# CPU_LPC1776_1.net
KiCad netlist of a schematic drawn in Altium Designer
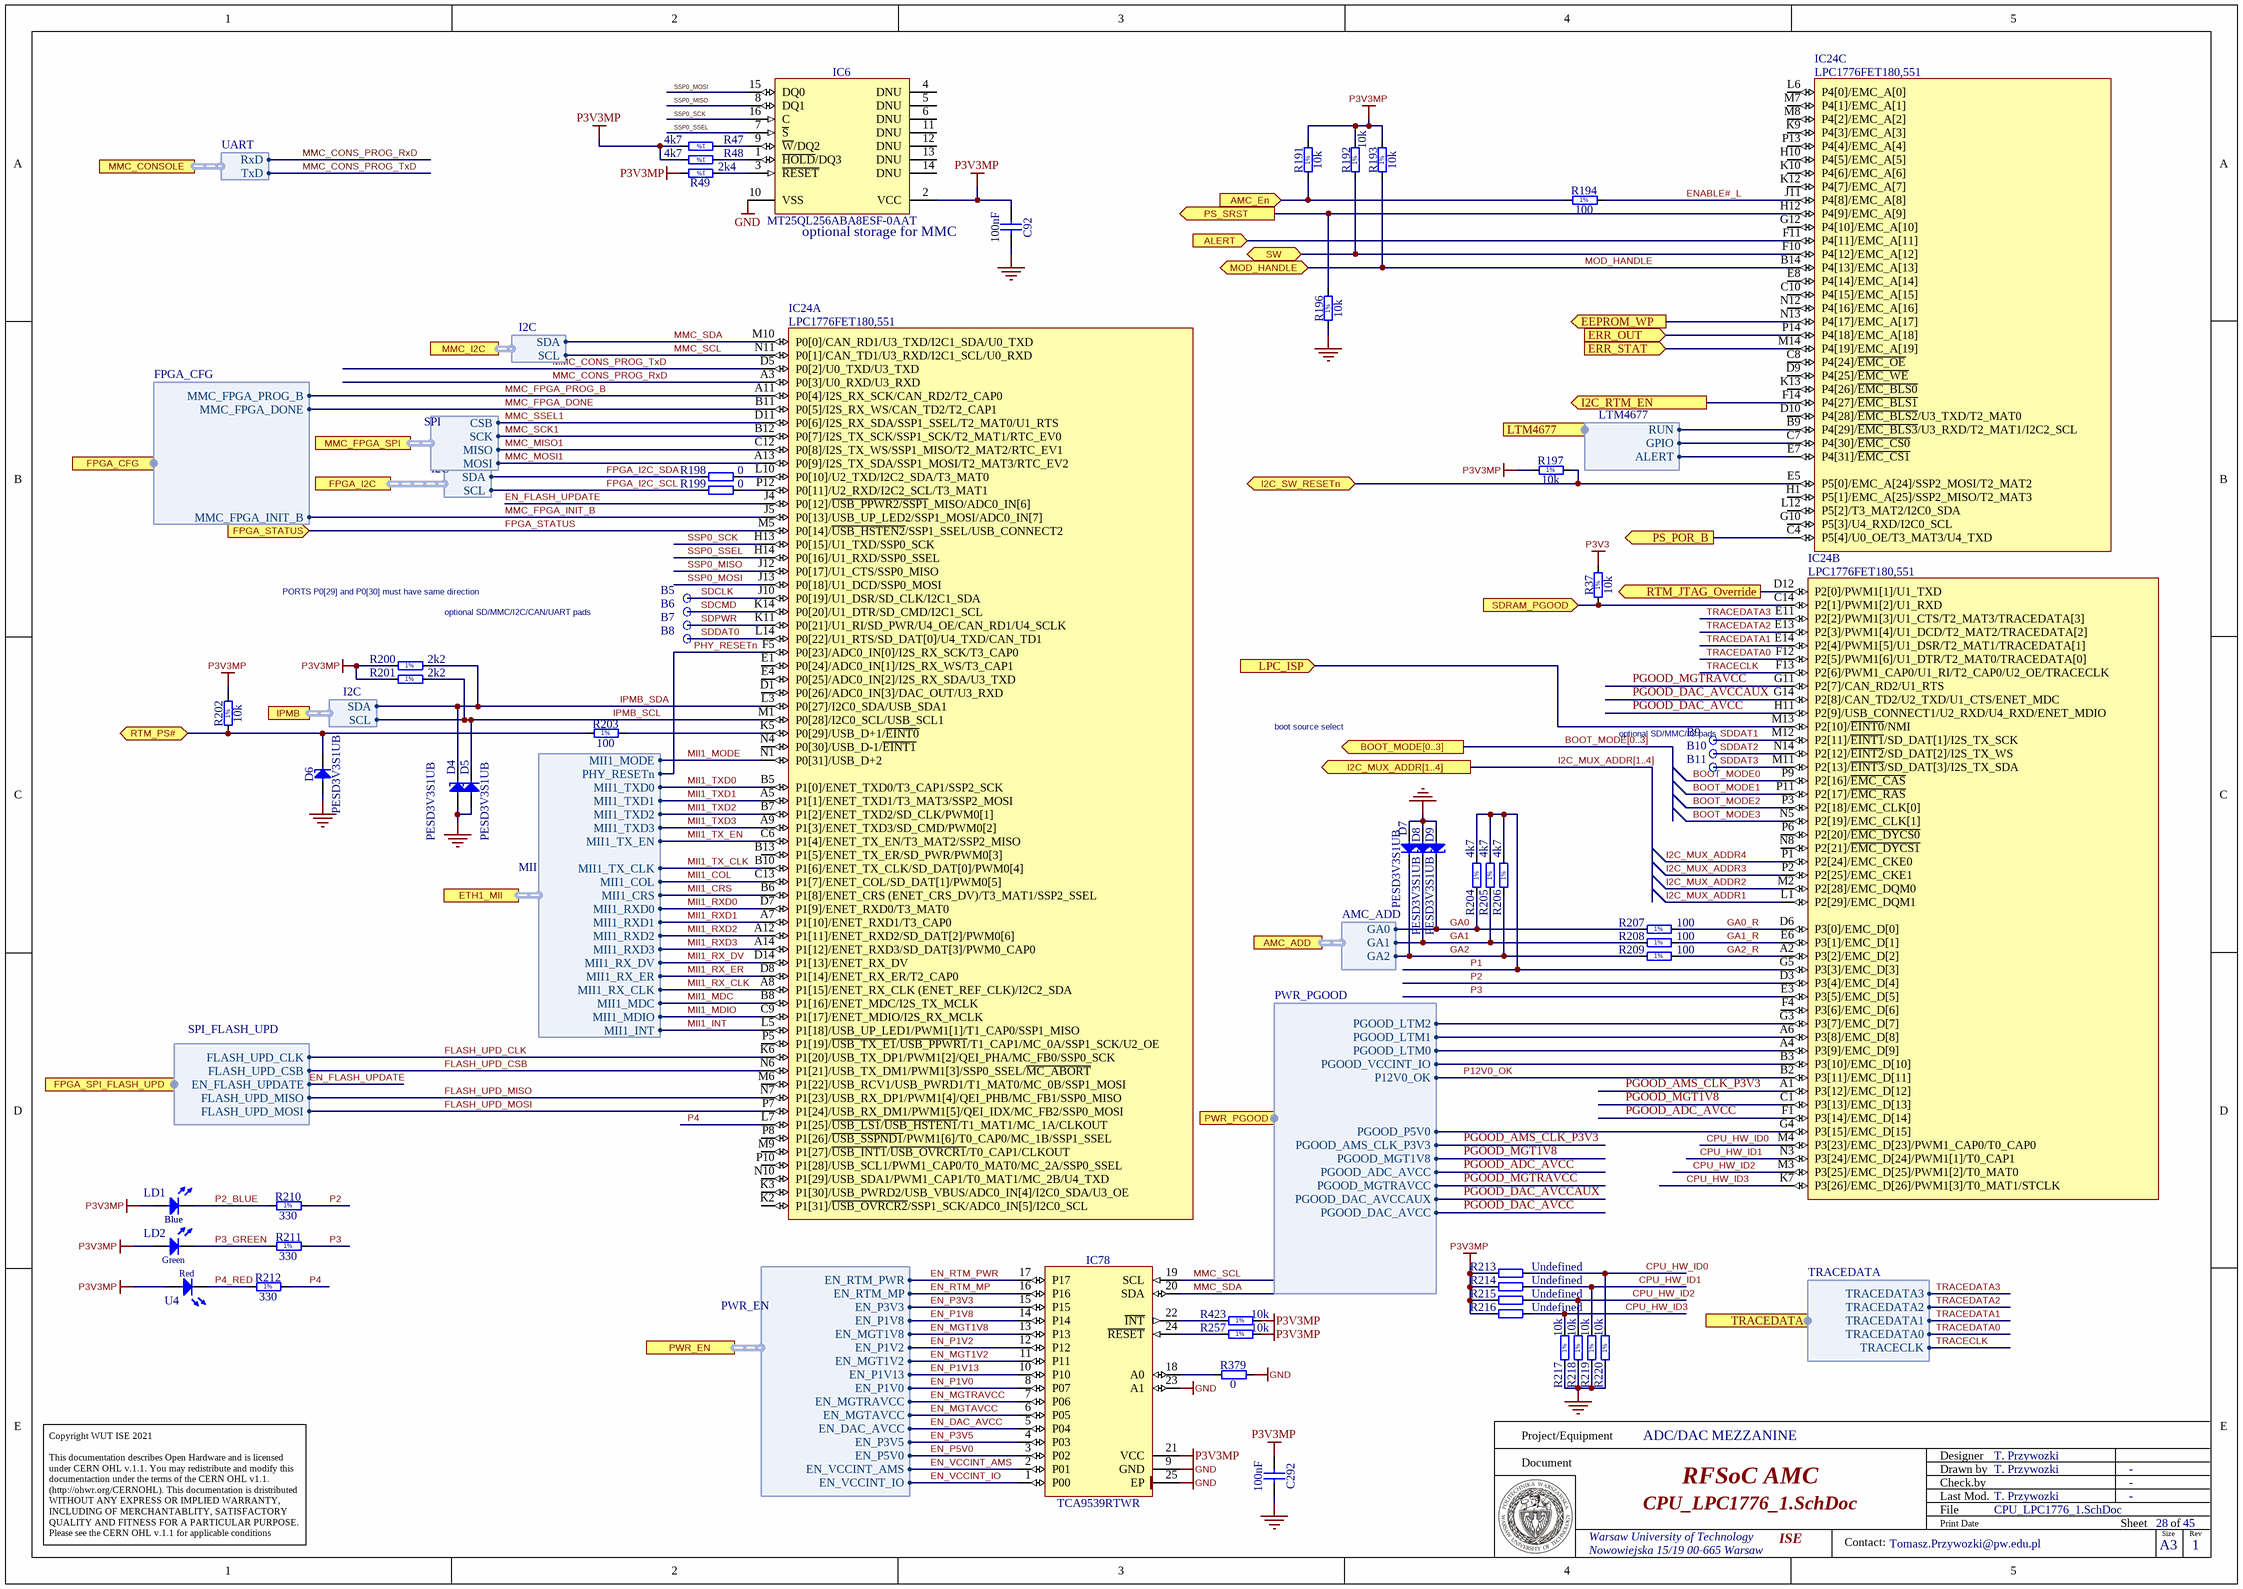
[diagram p0: CPU_LPC1776_1.SchDoc]

(export (version "E")
  (design (tool "Eeschema 10.0.6"))
  (components
    (comp (ref "B5")
      (value "SMD_PAD_D1MM")
      (footprint "C100")
      (libsource (lib "altium-import") (part "root_0__*"))
    )
    (comp (ref "B6")
      (value "SMD_PAD_D1MM")
      (footprint "C100")
      (libsource (lib "altium-import") (part "root_0__*"))
    )
    (comp (ref "B7")
      (value "SMD_PAD_D1MM")
      (footprint "C100")
      (libsource (lib "altium-import") (part "root_0__*"))
    )
    (comp (ref "B8")
      (value "SMD_PAD_D1MM")
      (footprint "C100")
      (libsource (lib "altium-import") (part "root_0__*"))
    )
    (comp (ref "B9")
      (value "SMD_PAD_D1MM")
      (footprint "C100")
      (libsource (lib "altium-import") (part "root_0__*"))
    )
    (comp (ref "B10")
      (value "SMD_PAD_D1MM")
      (footprint "C100")
      (libsource (lib "altium-import") (part "root_0__*"))
    )
    (comp (ref "B11")
      (value "SMD_PAD_D1MM")
      (footprint "C100")
      (libsource (lib "altium-import") (part "root_0__*"))
    )
    (comp (ref "C92")
      (value "100nF")
      (footprint "CAPC0603X33N")
      (description "Non-polarised capacitor")
      (fields
        (field (name "MANUFACTURER PART NUMBER") "CC0201_100NF_6.3V_10%_X5R")
        (field (name "MANUFACTURER") "GENERIC")
        (field (name "AUTHOR") "CERN DEM JLC")
      )
      (libsource (lib "Capacitors") (part "Capacitor - non polarized"))
    )
    (comp (ref "C292")
      (value "100nF")
      (footprint "CAPC0603X33N")
      (description "Non-polarised capacitor")
      (fields
        (field (name "MANUFACTURER PART NUMBER") "CC0201_100NF_6.3V_10%_X5R")
        (field (name "MANUFACTURER") "GENERIC")
        (field (name "AUTHOR") "CERN DEM JLC")
      )
      (libsource (lib "Capacitors") (part "Capacitor - non polarized"))
    )
    (comp (ref "D4")
      (value "PESD3V3S1UB")
      (footprint "SODFL1608X65N")
      (description "ESD protection diode")
      (fields
        (field (name "MANUFACTURER") "NXP SEMICONDUCTORS")
        (field (name "VOLTAGE") "3V3")
        (field (name "AUTHOR") "CERN DEM JLC")
      )
      (libsource (lib "ICs And Semiconductors") (part "Diode ESD"))
    )
    (comp (ref "D5")
      (value "PESD3V3S1UB")
      (footprint "SODFL1608X65N")
      (description "ESD protection diode")
      (fields
        (field (name "MANUFACTURER") "NXP SEMICONDUCTORS")
        (field (name "VOLTAGE") "3V3")
        (field (name "AUTHOR") "CERN DEM JLC")
      )
      (libsource (lib "ICs And Semiconductors") (part "Diode ESD"))
    )
    (comp (ref "D6")
      (value "PESD3V3S1UB")
      (footprint "SODFL1608X65N")
      (description "ESD protection diode")
      (fields
        (field (name "MANUFACTURER") "NXP SEMICONDUCTORS")
        (field (name "VOLTAGE") "3V3")
        (field (name "AUTHOR") "CERN DEM JLC")
      )
      (libsource (lib "ICs And Semiconductors") (part "Diode ESD"))
    )
    (comp (ref "D7")
      (value "PESD3V3S1UB")
      (footprint "SODFL1608X65N")
      (description "ESD protection diode")
      (fields
        (field (name "MANUFACTURER") "NXP SEMICONDUCTORS")
        (field (name "VOLTAGE") "3V3")
        (field (name "AUTHOR") "CERN DEM JLC")
      )
      (libsource (lib "ICs And Semiconductors") (part "Diode ESD"))
    )
    (comp (ref "D8")
      (value "PESD3V3S1UB")
      (footprint "SODFL1608X65N")
      (description "ESD protection diode")
      (fields
        (field (name "MANUFACTURER") "NXP SEMICONDUCTORS")
        (field (name "VOLTAGE") "3V3")
        (field (name "AUTHOR") "CERN DEM JLC")
      )
      (libsource (lib "ICs And Semiconductors") (part "Diode ESD"))
    )
    (comp (ref "D9")
      (value "PESD3V3S1UB")
      (footprint "SODFL1608X65N")
      (description "ESD protection diode")
      (fields
        (field (name "MANUFACTURER") "NXP SEMICONDUCTORS")
        (field (name "VOLTAGE") "3V3")
        (field (name "AUTHOR") "CERN DEM JLC")
      )
      (libsource (lib "ICs And Semiconductors") (part "Diode ESD"))
    )
    (comp (ref "IC6")
      (value "MT25QL256ABA8ESF-0AAT")
      (footprint "SOIC127P1030X265-16N")
      (description "256Mbit (32MB), 2.7V-3.6V, Multiple I/O Serial NOR Flash Memory,with Reset# & Hold#")
      (fields (field (name "MANUFACTURER") "MICRON TECHNOLOGY") (field (name "AUTHOR") "CERN DEM JLC"))
      (libsource (lib "ICs And Semiconductors") (part "MT25QL256ABA8ESF"))
    )
    (comp (ref "IC24")
      (value "LPC1776FET180,551")
      (footprint "BGA180C80P14X14_1200X1200X120")
      (fields (field (name "MANUFACTURER") "NXP SEMICONDUCTORS") (field (name "AUTHOR") "CERN DEM JMW"))
      (libsource (lib "ICs And Semiconductors") (part "LPC1776FET180,551"))
    )
    (comp (ref "IC78")
      (value "TCA9539RTWR")
      (footprint "QFN50P400X400X80-25N-S255")
      (description "Low-Voltage 16-Bit I2C and SMBus I/O Expander")
      (fields (field (name "MANUFACTURER") "TEXAS INSTRUMENTS") (field (name "AUTHOR") "CERN DEM MR"))
      (libsource (lib "ICs And Semiconductors") (part "TCA9539RTWR"))
    )
    (comp (ref "LD1")
      (value "Blue")
      (footprint "LED_AVAGO_HSMR-C120")
      (description "LED Blue 1C 2A")
      (fields
        (field (name "MANUFACTURER PART NUMBER") "HSMR-C120")
        (field (name "MANUFACTURER") "AVAGO TECHNOLOGIES")
        (field (name "AUTHOR") "CERN DEM JLC")
      )
      (libsource (lib "ICs And Semiconductors") (part "LED Blue 1C 2A"))
    )
    (comp (ref "LD2")
      (value "Green")
      (footprint "LED_AVAGO_HSME-C120")
      (description "LED Green 1C 2A")
      (fields
        (field (name "MANUFACTURER PART NUMBER") "HSME-C120")
        (field (name "MANUFACTURER") "AVAGO TECHNOLOGIES")
        (field (name "AUTHOR") "CERN DEM JMW")
      )
      (libsource (lib "ICs And Semiconductors") (part "LED Green 1C 2A"))
    )
    (comp (ref "R37")
      (value "10k")
      (footprint "RESC1005X40N")
      (description "Resistor - 1%")
      (fields
        (field (name "MANUFACTURER PART NUMBER") "R0402_10K_1%_0.0625W_100PPM")
        (field (name "MANUFACTURER") "GENERIC")
        (field (name "AUTHOR") "CERN DEM JLC")
      )
      (libsource (lib "Resistors") (part "Resistor - 1%"))
    )
    (comp (ref "R47")
      (value "4k7")
      (footprint "RESC1005X40N")
      (description "Resistor - 1%")
      (fields
        (field (name "MANUFACTURER PART NUMBER") "R0402_4K7_1%_0.0625W_100PPM")
        (field (name "MANUFACTURER") "GENERIC")
        (field (name "AUTHOR") "CERN DEM JLC")
      )
      (libsource (lib "Resistors") (part "Resistor - 1%"))
    )
    (comp (ref "R48")
      (value "4k7")
      (footprint "RESC1005X40N")
      (description "Resistor - 1%")
      (fields
        (field (name "MANUFACTURER PART NUMBER") "R0402_4K7_1%_0.0625W_100PPM")
        (field (name "MANUFACTURER") "GENERIC")
        (field (name "AUTHOR") "CERN DEM JLC")
      )
      (libsource (lib "Resistors") (part "Resistor - 1%"))
    )
    (comp (ref "R49")
      (value "2k4")
      (footprint "RESC1005X40N")
      (description "Resistor - 1%")
      (fields
        (field (name "MANUFACTURER PART NUMBER") "R0402_2K4_1%_0.0625W_100PPM")
        (field (name "MANUFACTURER") "GENERIC")
        (field (name "AUTHOR") "CERN DEM JLC")
      )
      (libsource (lib "Resistors") (part "Resistor - 1%"))
    )
    (comp (ref "R191")
      (value "10k")
      (footprint "RESC1005X40N")
      (description "Resistor - 1%")
      (fields
        (field (name "MANUFACTURER PART NUMBER") "R0402_10K_1%_0.0625W_100PPM")
        (field (name "MANUFACTURER") "GENERIC")
        (field (name "AUTHOR") "CERN DEM JLC")
      )
      (libsource (lib "Resistors") (part "Resistor - 1%"))
    )
    (comp (ref "R192")
      (value "10k")
      (footprint "RESC1005X40N")
      (description "Resistor - 1%")
      (fields
        (field (name "MANUFACTURER PART NUMBER") "R0402_10K_1%_0.0625W_100PPM")
        (field (name "MANUFACTURER") "GENERIC")
        (field (name "AUTHOR") "CERN DEM JLC")
      )
      (libsource (lib "Resistors") (part "Resistor - 1%"))
    )
    (comp (ref "R193")
      (value "10k")
      (footprint "RESC1005X40N")
      (description "Resistor - 1%")
      (fields
        (field (name "MANUFACTURER PART NUMBER") "R0402_10K_1%_0.0625W_100PPM")
        (field (name "MANUFACTURER") "GENERIC")
        (field (name "AUTHOR") "CERN DEM JLC")
      )
      (libsource (lib "Resistors") (part "Resistor - 1%"))
    )
    (comp (ref "R194")
      (value "100")
      (footprint "RESC1005X40N")
      (description "Resistor - 1%")
      (fields
        (field (name "MANUFACTURER PART NUMBER") "R0402_100R_1%_0.1W_100PPM_50V")
        (field (name "MANUFACTURER") "GENERIC")
        (field (name "AUTHOR") "CERN DEM JLC")
      )
      (libsource (lib "Resistors") (part "Resistor - 1%"))
    )
    (comp (ref "R196")
      (value "10k")
      (footprint "RESC1005X40N")
      (description "Resistor - 1%")
      (fields
        (field (name "MANUFACTURER PART NUMBER") "R0402_10K_1%_0.0625W_100PPM")
        (field (name "MANUFACTURER") "GENERIC")
        (field (name "AUTHOR") "CERN DEM JLC")
      )
      (libsource (lib "Resistors") (part "Resistor - 1%"))
    )
    (comp (ref "R197")
      (value "10k")
      (footprint "RESC1005X40N")
      (description "Resistor - 1%")
      (fields
        (field (name "MANUFACTURER PART NUMBER") "R0402_10K_1%_0.0625W_100PPM")
        (field (name "MANUFACTURER") "GENERIC")
        (field (name "AUTHOR") "CERN DEM JLC")
      )
      (libsource (lib "Resistors") (part "Resistor - 1%"))
    )
    (comp (ref "R198")
      (value "0")
      (footprint "RESC1005X40N")
      (description "Resistor")
      (fields
        (field (name "MANUFACTURER PART NUMBER") "R0402_0R_JUMPER")
        (field (name "MANUFACTURER") "GENERIC")
        (field (name "AUTHOR") "CERN DEM JLC")
      )
      (libsource (lib "Resistors") (part "Resistor"))
    )
    (comp (ref "R199")
      (value "0")
      (footprint "RESC1005X40N")
      (description "Resistor")
      (fields
        (field (name "MANUFACTURER PART NUMBER") "R0402_0R_JUMPER")
        (field (name "MANUFACTURER") "GENERIC")
        (field (name "AUTHOR") "CERN DEM JLC")
      )
      (libsource (lib "Resistors") (part "Resistor"))
    )
    (comp (ref "R200")
      (value "2k2")
      (footprint "RESC1005X40N")
      (description "Resistor - 1%")
      (fields
        (field (name "MANUFACTURER PART NUMBER") "R0402_2K2_1%_0.0625W_100PPM")
        (field (name "MANUFACTURER") "GENERIC")
        (field (name "AUTHOR") "CERN DEM JLC")
      )
      (libsource (lib "Resistors") (part "Resistor - 1%"))
    )
    (comp (ref "R201")
      (value "2k2")
      (footprint "RESC1005X40N")
      (description "Resistor - 1%")
      (fields
        (field (name "MANUFACTURER PART NUMBER") "R0402_2K2_1%_0.0625W_100PPM")
        (field (name "MANUFACTURER") "GENERIC")
        (field (name "AUTHOR") "CERN DEM JLC")
      )
      (libsource (lib "Resistors") (part "Resistor - 1%"))
    )
    (comp (ref "R202")
      (value "10k")
      (footprint "RESC1005X40N")
      (description "Resistor - 1%")
      (fields
        (field (name "MANUFACTURER PART NUMBER") "R0402_10K_1%_0.0625W_100PPM")
        (field (name "MANUFACTURER") "GENERIC")
        (field (name "AUTHOR") "CERN DEM JLC")
      )
      (libsource (lib "Resistors") (part "Resistor - 1%"))
    )
    (comp (ref "R203")
      (value "100")
      (footprint "RESC1005X40N")
      (description "Resistor - 1%")
      (fields
        (field (name "MANUFACTURER PART NUMBER") "R0402_100R_1%_0.1W_100PPM_50V")
        (field (name "MANUFACTURER") "GENERIC")
        (field (name "AUTHOR") "CERN DEM JLC")
      )
      (libsource (lib "Resistors") (part "Resistor - 1%"))
    )
    (comp (ref "R204")
      (value "4k7")
      (footprint "RESC1005X40N")
      (description "Resistor - 1%")
      (fields
        (field (name "MANUFACTURER PART NUMBER") "R0402_4K7_1%_0.0625W_100PPM")
        (field (name "MANUFACTURER") "GENERIC")
        (field (name "AUTHOR") "CERN DEM JLC")
      )
      (libsource (lib "Resistors") (part "Resistor - 1%"))
    )
    (comp (ref "R205")
      (value "4k7")
      (footprint "RESC1005X40N")
      (description "Resistor - 1%")
      (fields
        (field (name "MANUFACTURER PART NUMBER") "R0402_4K7_1%_0.0625W_100PPM")
        (field (name "MANUFACTURER") "GENERIC")
        (field (name "AUTHOR") "CERN DEM JLC")
      )
      (libsource (lib "Resistors") (part "Resistor - 1%"))
    )
    (comp (ref "R206")
      (value "4k7")
      (footprint "RESC1005X40N")
      (description "Resistor - 1%")
      (fields
        (field (name "MANUFACTURER PART NUMBER") "R0402_4K7_1%_0.0625W_100PPM")
        (field (name "MANUFACTURER") "GENERIC")
        (field (name "AUTHOR") "CERN DEM JLC")
      )
      (libsource (lib "Resistors") (part "Resistor - 1%"))
    )
    (comp (ref "R207")
      (value "100")
      (footprint "RESC1005X40N")
      (description "Resistor - 1%")
      (fields
        (field (name "MANUFACTURER PART NUMBER") "R0402_100R_1%_0.1W_100PPM_50V")
        (field (name "MANUFACTURER") "GENERIC")
        (field (name "AUTHOR") "CERN DEM JLC")
      )
      (libsource (lib "Resistors") (part "Resistor - 1%"))
    )
    (comp (ref "R208")
      (value "100")
      (footprint "RESC1005X40N")
      (description "Resistor - 1%")
      (fields
        (field (name "MANUFACTURER PART NUMBER") "R0402_100R_1%_0.1W_100PPM_50V")
        (field (name "MANUFACTURER") "GENERIC")
        (field (name "AUTHOR") "CERN DEM JLC")
      )
      (libsource (lib "Resistors") (part "Resistor - 1%"))
    )
    (comp (ref "R209")
      (value "100")
      (footprint "RESC1005X40N")
      (description "Resistor - 1%")
      (fields
        (field (name "MANUFACTURER PART NUMBER") "R0402_100R_1%_0.1W_100PPM_50V")
        (field (name "MANUFACTURER") "GENERIC")
        (field (name "AUTHOR") "CERN DEM JLC")
      )
      (libsource (lib "Resistors") (part "Resistor - 1%"))
    )
    (comp (ref "R210")
      (value "330")
      (footprint "RESC1005X40N")
      (description "Resistor - 1%")
      (fields
        (field (name "MANUFACTURER PART NUMBER") "R0402_330R_1%_0.0625W_100PPM")
        (field (name "MANUFACTURER") "GENERIC")
        (field (name "AUTHOR") "CERN DEM JLC")
      )
      (libsource (lib "Resistors") (part "Resistor - 1%"))
    )
    (comp (ref "R211")
      (value "330")
      (footprint "RESC1005X40N")
      (description "Resistor - 1%")
      (fields
        (field (name "MANUFACTURER PART NUMBER") "R0402_330R_1%_0.0625W_100PPM")
        (field (name "MANUFACTURER") "GENERIC")
        (field (name "AUTHOR") "CERN DEM JLC")
      )
      (libsource (lib "Resistors") (part "Resistor - 1%"))
    )
    (comp (ref "R212")
      (value "330")
      (footprint "RESC1005X40N")
      (description "Resistor - 1%")
      (fields
        (field (name "MANUFACTURER PART NUMBER") "R0402_330R_1%_0.0625W_100PPM")
        (field (name "MANUFACTURER") "GENERIC")
        (field (name "AUTHOR") "CERN DEM JLC")
      )
      (libsource (lib "Resistors") (part "Resistor - 1%"))
    )
    (comp (ref "R213")
      (value "Undefined")
      (footprint "RESC1005X40N")
      (description "Resistor")
      (fields (field (name "PART NUMBER") "R0402_NO-VALUE") (field (name "AUTHOR") "CERN DEM JLC"))
      (libsource (lib "Resistors") (part "Resistor"))
    )
    (comp (ref "R214")
      (value "Undefined")
      (footprint "RESC1005X40N")
      (description "Resistor")
      (fields (field (name "PART NUMBER") "R0402_NO-VALUE") (field (name "AUTHOR") "CERN DEM JLC"))
      (libsource (lib "Resistors") (part "Resistor"))
    )
    (comp (ref "R215")
      (value "Undefined")
      (footprint "RESC1005X40N")
      (description "Resistor")
      (fields (field (name "PART NUMBER") "R0402_NO-VALUE") (field (name "AUTHOR") "CERN DEM JLC"))
      (libsource (lib "Resistors") (part "Resistor"))
    )
    (comp (ref "R216")
      (value "Undefined")
      (footprint "RESC1005X40N")
      (description "Resistor")
      (fields (field (name "PART NUMBER") "R0402_NO-VALUE") (field (name "AUTHOR") "CERN DEM JLC"))
      (libsource (lib "Resistors") (part "Resistor"))
    )
    (comp (ref "R217")
      (value "10k")
      (footprint "RESC1005X40N")
      (description "Resistor - 1%")
      (fields
        (field (name "MANUFACTURER PART NUMBER") "R0402_10K_1%_0.0625W_100PPM")
        (field (name "MANUFACTURER") "GENERIC")
        (field (name "AUTHOR") "CERN DEM JLC")
      )
      (libsource (lib "Resistors") (part "Resistor - 1%"))
    )
    (comp (ref "R218")
      (value "10k")
      (footprint "RESC1005X40N")
      (description "Resistor - 1%")
      (fields
        (field (name "MANUFACTURER PART NUMBER") "R0402_10K_1%_0.0625W_100PPM")
        (field (name "MANUFACTURER") "GENERIC")
        (field (name "AUTHOR") "CERN DEM JLC")
      )
      (libsource (lib "Resistors") (part "Resistor - 1%"))
    )
    (comp (ref "R219")
      (value "10k")
      (footprint "RESC1005X40N")
      (description "Resistor - 1%")
      (fields
        (field (name "MANUFACTURER PART NUMBER") "R0402_10K_1%_0.0625W_100PPM")
        (field (name "MANUFACTURER") "GENERIC")
        (field (name "AUTHOR") "CERN DEM JLC")
      )
      (libsource (lib "Resistors") (part "Resistor - 1%"))
    )
    (comp (ref "R220")
      (value "10k")
      (footprint "RESC1005X40N")
      (description "Resistor - 1%")
      (fields
        (field (name "MANUFACTURER PART NUMBER") "R0402_10K_1%_0.0625W_100PPM")
        (field (name "MANUFACTURER") "GENERIC")
        (field (name "AUTHOR") "CERN DEM JLC")
      )
      (libsource (lib "Resistors") (part "Resistor - 1%"))
    )
    (comp (ref "R257")
      (value "10k")
      (footprint "RESC1005X40N")
      (description "Resistor - 1%")
      (fields
        (field (name "MANUFACTURER PART NUMBER") "R0402_10K_1%_0.0625W_100PPM")
        (field (name "MANUFACTURER") "GENERIC")
        (field (name "AUTHOR") "CERN DEM JLC")
      )
      (libsource (lib "Resistors") (part "Resistor - 1%"))
    )
    (comp (ref "R379")
      (value "0")
      (footprint "RESC1005X40N")
      (description "Resistor")
      (fields
        (field (name "PART NUMBER") "R0402_0R_JUMPER")
        (field (name "MANUFACTURER") "GENERIC")
        (field (name "AUTHOR") "CERN DEM JLC")
      )
      (libsource (lib "Resistors") (part "Resistor"))
    )
    (comp (ref "R423")
      (value "10k")
      (footprint "RESC1005X40N")
      (description "Resistor - 1%")
      (fields
        (field (name "MANUFACTURER PART NUMBER") "R0402_10K_1%_0.0625W_100PPM")
        (field (name "MANUFACTURER") "GENERIC")
        (field (name "AUTHOR") "CERN DEM JLC")
      )
      (libsource (lib "Resistors") (part "Resistor - 1%"))
    )
    (comp (ref "U4")
      (value "Red")
      (footprint "LED_OSRAM_LS Q976")
      (description "LED Red 1C 2A")
      (fields
        (field (name "MANUFACTURER PART NUMBER") "LS Q976-NR-1")
        (field (name "MANUFACTURER") "OSRAM")
        (field (name "AUTHOR") "CERN DEM JLC")
      )
      (libsource (lib "ICs And Semiconductors") (part "LED Red 1C 2A"))
    )
  )
  (nets
    (net (code "12") (name "/ALERT") (class "Default")
      (node (ref "IC24") (pin "F11") (pinfunction "P4[11]/EMC_A[11]_F11") (pintype "bidirectional"))
    )
    (net (code "13") (name "/AMC_En") (class "Default")
      (node (ref "R191") (pin "1") (pinfunction "1_1") (pintype "passive"))
      (node (ref "R194") (pin "1") (pinfunction "1_1") (pintype "passive"))
    )
    (net (code "14") (name "/BOOT_MODE0") (class "Default")
      (node (ref "IC24") (pin "P9") (pinfunction "P2[16]/~{EMC_CAS}_P9") (pintype "bidirectional"))
    )
    (net (code "15") (name "/BOOT_MODE1") (class "Default")
      (node (ref "IC24") (pin "P11") (pinfunction "P2[17]/~{EMC_RAS}_P11") (pintype "bidirectional"))
    )
    (net (code "16") (name "/BOOT_MODE2") (class "Default")
      (node (ref "IC24") (pin "P3") (pinfunction "P2[18]/EMC_CLK[0]_P3") (pintype "bidirectional"))
    )
    (net (code "17") (name "/BOOT_MODE3") (class "Default")
      (node (ref "IC24") (pin "N5") (pinfunction "P2[19]/EMC_CLK[1]_N5") (pintype "bidirectional"))
    )
    (net (code "19") (name "/CPU_HW_ID0") (class "Default")
      (node (ref "IC24") (pin "M4") (pinfunction "P3[23]/EMC_D[23]/PWM1_CAP0/T0_CAP0_M4") (pintype "bidirectional"))
      (node (ref "R213") (pin "2") (pinfunction "2_2") (pintype "passive"))
      (node (ref "R220") (pin "2") (pinfunction "2_2") (pintype "passive"))
    )
    (net (code "20") (name "/CPU_HW_ID1") (class "Default")
      (node (ref "IC24") (pin "N3") (pinfunction "P3[24]/EMC_D[24]/PWM1[1]/T0_CAP1_N3") (pintype "bidirectional"))
      (node (ref "R214") (pin "2") (pinfunction "2_2") (pintype "passive"))
      (node (ref "R219") (pin "2") (pinfunction "2_2") (pintype "passive"))
    )
    (net (code "21") (name "/CPU_HW_ID2") (class "Default")
      (node (ref "IC24") (pin "M3") (pinfunction "P3[25]/EMC_D[25]/PWM1[2]/T0_MAT0_M3") (pintype "bidirectional"))
      (node (ref "R215") (pin "2") (pinfunction "2_2") (pintype "passive"))
      (node (ref "R218") (pin "2") (pinfunction "2_2") (pintype "passive"))
    )
    (net (code "22") (name "/CPU_HW_ID3") (class "Default")
      (node (ref "IC24") (pin "K7") (pinfunction "P3[26]/EMC_D[26]/PWM1[3]/T0_MAT1/STCLK_K7") (pintype "bidirectional"))
      (node (ref "R216") (pin "2") (pinfunction "2_2") (pintype "passive"))
      (node (ref "R217") (pin "2") (pinfunction "2_2") (pintype "passive"))
    )
    (net (code "23") (name "/EEPROM_WP") (class "Default")
      (node (ref "IC24") (pin "N13") (pinfunction "P4[17]/EMC_A[17]_N13") (pintype "bidirectional"))
    )
    (net (code "24") (name "/ENABLE#_L") (class "Default")
      (node (ref "IC24") (pin "J11") (pinfunction "P4[8]/EMC_A[8]_J11") (pintype "bidirectional"))
      (node (ref "R194") (pin "2") (pinfunction "2_2") (pintype "passive"))
    )
    (net (code "25") (name "/EN_DAC_AVCC") (class "Default")
      (node (ref "IC78") (pin "5") (pinfunction "P04_5") (pintype "bidirectional"))
    )
    (net (code "26") (name "/EN_FLASH_UPDATE") (class "Default")
      (node (ref "IC24") (pin "J4") (pinfunction "P0[12]/~{USB_PPWR2/SSP1}_MISO/ADC0_IN[6]_J4") (pintype "bidirectional"))
    )
    (net (code "27") (name "/EN_MGT1V2") (class "Default")
      (node (ref "IC78") (pin "11") (pinfunction "P11_11") (pintype "bidirectional"))
    )
    (net (code "28") (name "/EN_MGT1V8") (class "Default")
      (node (ref "IC78") (pin "13") (pinfunction "P13_13") (pintype "bidirectional"))
    )
    (net (code "29") (name "/EN_MGTAVCC") (class "Default")
      (node (ref "IC78") (pin "6") (pinfunction "P05_6") (pintype "bidirectional"))
    )
    (net (code "30") (name "/EN_MGTRAVCC") (class "Default")
      (node (ref "IC78") (pin "7") (pinfunction "P06_7") (pintype "bidirectional"))
    )
    (net (code "31") (name "/EN_P1V0") (class "Default")
      (node (ref "IC78") (pin "8") (pinfunction "P07_8") (pintype "bidirectional"))
    )
    (net (code "32") (name "/EN_P1V2") (class "Default")
      (node (ref "IC78") (pin "12") (pinfunction "P12_12") (pintype "bidirectional"))
    )
    (net (code "33") (name "/EN_P1V8") (class "Default")
      (node (ref "IC78") (pin "14") (pinfunction "P14_14") (pintype "bidirectional"))
    )
    (net (code "34") (name "/EN_P1V13") (class "Default")
      (node (ref "IC78") (pin "10") (pinfunction "P10_10") (pintype "bidirectional"))
    )
    (net (code "35") (name "/EN_P3V3") (class "Default")
      (node (ref "IC78") (pin "15") (pinfunction "P15_15") (pintype "bidirectional"))
    )
    (net (code "36") (name "/EN_P3V5") (class "Default")
      (node (ref "IC78") (pin "4") (pinfunction "P03_4") (pintype "bidirectional"))
    )
    (net (code "37") (name "/EN_P5V0") (class "Default")
      (node (ref "IC78") (pin "3") (pinfunction "P02_3") (pintype "bidirectional"))
    )
    (net (code "38") (name "/EN_RTM_MP") (class "Default")
      (node (ref "IC78") (pin "16") (pinfunction "P16_16") (pintype "bidirectional"))
    )
    (net (code "39") (name "/EN_RTM_PWR") (class "Default")
      (node (ref "IC78") (pin "17") (pinfunction "P17_17") (pintype "bidirectional"))
    )
    (net (code "40") (name "/EN_VCCINT_AMS") (class "Default")
      (node (ref "IC78") (pin "2") (pinfunction "P01_2") (pintype "bidirectional"))
    )
    (net (code "41") (name "/EN_VCCINT_IO") (class "Default")
      (node (ref "IC78") (pin "1") (pinfunction "P00_1") (pintype "bidirectional"))
    )
    (net (code "42") (name "/ERR_OUT") (class "Default")
      (node (ref "IC24") (pin "P14") (pinfunction "P4[18]/EMC_A[18]_P14") (pintype "bidirectional"))
    )
    (net (code "43") (name "/ERR_STAT") (class "Default")
      (node (ref "IC24") (pin "M14") (pinfunction "P4[19]/EMC_A[19]_M14") (pintype "bidirectional"))
    )
    (net (code "44") (name "/FLASH_UPD_CLK") (class "Default")
      (node (ref "IC24") (pin "K6") (pinfunction "P1[20]/USB_TX_DP1/PWM1[2]/QEI_PHA/MC_FB0/SSP0_SCK_K6") (pintype "bidirectional"))
    )
    (net (code "45") (name "/FLASH_UPD_CSB") (class "Default")
      (node (ref "IC24") (pin "N6") (pinfunction "P1[21]/USB_TX_DM1/PWM1[3]/SSP0_SSEL/~{MC_ABORT}_N6") (pintype "bidirectional"))
    )
    (net (code "46") (name "/FLASH_UPD_MISO") (class "Default")
      (node (ref "IC24") (pin "N7") (pinfunction "P1[23]/USB_RX_DP1/PWM1[4]/QEI_PHB/MC_FB1/SSP0_MISO_N7") (pintype "bidirectional"))
    )
    (net (code "47") (name "/FLASH_UPD_MOSI") (class "Default")
      (node (ref "IC24") (pin "P7") (pinfunction "P1[24]/USB_RX_DM1/PWM1[5]/QEI_IDX/MC_FB2/SSP0_MOSI_P7") (pintype "bidirectional"))
    )
    (net (code "49") (name "/FPGA_I2C_SCL") (class "Default")
      (node (ref "R199") (pin "1") (pinfunction "1_1") (pintype "passive"))
    )
    (net (code "50") (name "/FPGA_I2C_SDA") (class "Default")
      (node (ref "R198") (pin "1") (pinfunction "1_1") (pintype "passive"))
    )
    (net (code "51") (name "/FPGA_STATUS") (class "Default")
      (node (ref "IC24") (pin "M5") (pinfunction "P0[14]/~{USB_HSTEN2}/SSP1_SSEL/USB_CONNECT2_M5") (pintype "bidirectional"))
    )
    (net (code "52") (name "/GA0") (class "Default")
      (node (ref "D9") (pin "1") (pinfunction "C_1") (pintype "passive"))
      (node (ref "R204") (pin "1") (pinfunction "1_1") (pintype "passive"))
      (node (ref "R207") (pin "1") (pinfunction "1_1") (pintype "passive"))
    )
    (net (code "53") (name "/GA0_R") (class "Default")
      (node (ref "IC24") (pin "D6") (pinfunction "P3[0]/EMC_D[0]_D6") (pintype "bidirectional"))
      (node (ref "R207") (pin "2") (pinfunction "2_2") (pintype "passive"))
    )
    (net (code "54") (name "/GA1") (class "Default")
      (node (ref "D8") (pin "1") (pinfunction "C_1") (pintype "passive"))
      (node (ref "R205") (pin "1") (pinfunction "1_1") (pintype "passive"))
      (node (ref "R208") (pin "1") (pinfunction "1_1") (pintype "passive"))
    )
    (net (code "55") (name "/GA1_R") (class "Default")
      (node (ref "IC24") (pin "E6") (pinfunction "P3[1]/EMC_D[1]_E6") (pintype "bidirectional"))
      (node (ref "R208") (pin "2") (pinfunction "2_2") (pintype "passive"))
    )
    (net (code "56") (name "/GA2") (class "Default")
      (node (ref "D7") (pin "1") (pinfunction "C_1") (pintype "passive"))
      (node (ref "R206") (pin "1") (pinfunction "1_1") (pintype "passive"))
      (node (ref "R209") (pin "1") (pinfunction "1_1") (pintype "passive"))
    )
    (net (code "57") (name "/GA2_R") (class "Default")
      (node (ref "IC24") (pin "A2") (pinfunction "P3[2]/EMC_D[2]_A2") (pintype "bidirectional"))
      (node (ref "R209") (pin "2") (pinfunction "2_2") (pintype "passive"))
    )
    (net (code "58") (name "/GPIO") (class "Default")
      (node (ref "IC24") (pin "C7") (pinfunction "P4[30]/~{EMC_CS0}_C7") (pintype "bidirectional"))
    )
    (net (code "59") (name "/I2C_MUX_ADDR1") (class "Default")
      (node (ref "IC24") (pin "L1") (pinfunction "P2[29]/EMC_DQM1_L1") (pintype "bidirectional"))
    )
    (net (code "60") (name "/I2C_MUX_ADDR2") (class "Default")
      (node (ref "IC24") (pin "M2") (pinfunction "P2[28]/EMC_DQM0_M2") (pintype "bidirectional"))
    )
    (net (code "61") (name "/I2C_MUX_ADDR3") (class "Default")
      (node (ref "IC24") (pin "P2") (pinfunction "P2[25]/EMC_CKE1_P2") (pintype "bidirectional"))
    )
    (net (code "62") (name "/I2C_MUX_ADDR4") (class "Default")
      (node (ref "IC24") (pin "P1") (pinfunction "P2[24]/EMC_CKE0_P1") (pintype "bidirectional"))
    )
    (net (code "64") (name "/I2C_RTM_EN") (class "Default")
      (node (ref "IC24") (pin "F14") (pinfunction "P4[27]/~{EMC_BLS1}_F14") (pintype "bidirectional"))
    )
    (net (code "65") (name "/I2C_SW_RESETn") (class "Default")
      (node (ref "IC24") (pin "E5") (pinfunction "P5[0]/EMC_A[24]/SSP2_MOSI/T2_MAT2_E5") (pintype "bidirectional"))
      (node (ref "R197") (pin "2") (pinfunction "2_2") (pintype "passive"))
    )
    (net (code "66") (name "/IPMB_SCL") (class "Default")
      (node (ref "D5") (pin "1") (pinfunction "C_1") (pintype "passive"))
      (node (ref "IC24") (pin "M1") (pinfunction "P0[28]/I2C0_SCL/USB_SCL1_M1") (pintype "bidirectional"))
      (node (ref "R201") (pin "2") (pinfunction "2_2") (pintype "passive"))
    )
    (net (code "67") (name "/IPMB_SDA") (class "Default")
      (node (ref "D4") (pin "1") (pinfunction "C_1") (pintype "passive"))
      (node (ref "IC24") (pin "L3") (pinfunction "P0[27]/I2C0_SDA/USB_SDA1_L3") (pintype "bidirectional"))
      (node (ref "R200") (pin "2") (pinfunction "2_2") (pintype "passive"))
    )
    (net (code "68") (name "/LPC_ISP") (class "Default")
      (node (ref "IC24") (pin "M13") (pinfunction "P2[10]/~{EINT0}/NMI_M13") (pintype "bidirectional"))
    )
    (net (code "69") (name "/MII1_COL") (class "Default")
      (node (ref "IC24") (pin "C13") (pinfunction "P1[7]/ENET_COL/SD_DAT[1]/PWM0[5]_C13") (pintype "bidirectional"))
    )
    (net (code "70") (name "/MII1_CRS") (class "Default")
      (node (ref "IC24") (pin "B6") (pinfunction "P1[8]/ENET_CRS_(ENET_CRS_DV)/T3_MAT1/SSP2_SSEL_B6") (pintype "bidirectional"))
    )
    (net (code "71") (name "/MII1_INT") (class "Default")
      (node (ref "IC24") (pin "L5") (pinfunction "P1[18]/USB_UP_LED1/PWM1[1]/T1_CAP0/SSP1_MISO_L5") (pintype "bidirectional"))
    )
    (net (code "72") (name "/MII1_MDC") (class "Default")
      (node (ref "IC24") (pin "B8") (pinfunction "P1[16]/ENET_MDC/I2S_TX_MCLK_B8") (pintype "bidirectional"))
    )
    (net (code "73") (name "/MII1_MDIO") (class "Default")
      (node (ref "IC24") (pin "C9") (pinfunction "P1[17]/ENET_MDIO/I2S_RX_MCLK_C9") (pintype "bidirectional"))
    )
    (net (code "74") (name "/MII1_MODE") (class "Default")
      (node (ref "IC24") (pin "N1") (pinfunction "P0[31]/USB_D+2_N1") (pintype "bidirectional"))
    )
    (net (code "75") (name "/MII1_RXD0") (class "Default")
      (node (ref "IC24") (pin "D7") (pinfunction "P1[9]/ENET_RXD0/T3_MAT0_D7") (pintype "bidirectional"))
    )
    (net (code "76") (name "/MII1_RXD1") (class "Default")
      (node (ref "IC24") (pin "A7") (pinfunction "P1[10]/ENET_RXD1/T3_CAP0_A7") (pintype "bidirectional"))
    )
    (net (code "77") (name "/MII1_RXD2") (class "Default")
      (node (ref "IC24") (pin "A12") (pinfunction "P1[11]/ENET_RXD2/SD_DAT[2]/PWM0[6]_A12") (pintype "bidirectional"))
    )
    (net (code "78") (name "/MII1_RXD3") (class "Default")
      (node (ref "IC24") (pin "A14") (pinfunction "P1[12]/ENET_RXD3/SD_DAT[3]/PWM0_CAP0_A14") (pintype "bidirectional"))
    )
    (net (code "79") (name "/MII1_RX_CLK") (class "Default")
      (node (ref "IC24") (pin "A8") (pinfunction "P1[15]/ENET_RX_CLK_(ENET_REF_CLK)/I2C2_SDA_A8") (pintype "bidirectional"))
    )
    (net (code "80") (name "/MII1_RX_DV") (class "Default")
      (node (ref "IC24") (pin "D14") (pinfunction "P1[13]/ENET_RX_DV_D14") (pintype "bidirectional"))
    )
    (net (code "81") (name "/MII1_RX_ER") (class "Default")
      (node (ref "IC24") (pin "D8") (pinfunction "P1[14]/ENET_RX_ER/T2_CAP0_D8") (pintype "bidirectional"))
    )
    (net (code "82") (name "/MII1_TXD0") (class "Default")
      (node (ref "IC24") (pin "B5") (pinfunction "P1[0]/ENET_TXD0/T3_CAP1/SSP2_SCK_B5") (pintype "bidirectional"))
    )
    (net (code "83") (name "/MII1_TXD1") (class "Default")
      (node (ref "IC24") (pin "A5") (pinfunction "P1[1]/ENET_TXD1/T3_MAT3/SSP2_MOSI_A5") (pintype "bidirectional"))
    )
    (net (code "84") (name "/MII1_TXD2") (class "Default")
      (node (ref "IC24") (pin "B7") (pinfunction "P1[2]/ENET_TXD2/SD_CLK/PWM0[1]_B7") (pintype "bidirectional"))
    )
    (net (code "85") (name "/MII1_TXD3") (class "Default")
      (node (ref "IC24") (pin "A9") (pinfunction "P1[3]/ENET_TXD3/SD_CMD/PWM0[2]_A9") (pintype "bidirectional"))
    )
    (net (code "86") (name "/MII1_TX_CLK") (class "Default")
      (node (ref "IC24") (pin "B10") (pinfunction "P1[6]/ENET_TX_CLK/SD_DAT[0]/PWM0[4]_B10") (pintype "bidirectional"))
    )
    (net (code "87") (name "/MII1_TX_EN") (class "Default")
      (node (ref "IC24") (pin "C6") (pinfunction "P1[4]/ENET_TX_EN/T3_MAT2/SSP2_MISO_C6") (pintype "bidirectional"))
    )
    (net (code "88") (name "/MMC_CONS_PROG_RxD") (class "Default")
      (node (ref "IC24") (pin "A3") (pinfunction "P0[3]/U0_RXD/U3_RXD_A3") (pintype "bidirectional"))
    )
    (net (code "89") (name "/MMC_CONS_PROG_TxD") (class "Default")
      (node (ref "IC24") (pin "D5") (pinfunction "P0[2]/U0_TXD/U3_TXD_D5") (pintype "bidirectional"))
    )
    (net (code "90") (name "/MMC_FPGA_DONE") (class "Default")
      (node (ref "IC24") (pin "B11") (pinfunction "P0[5]/I2S_RX_WS/CAN_TD2/T2_CAP1_B11") (pintype "bidirectional"))
    )
    (net (code "91") (name "/MMC_FPGA_INIT_B") (class "Default")
      (node (ref "IC24") (pin "J5") (pinfunction "P0[13]/USB_UP_LED2/SSP1_MOSI/ADC0_IN[7]_J5") (pintype "bidirectional"))
    )
    (net (code "92") (name "/MMC_FPGA_PROG_B") (class "Default")
      (node (ref "IC24") (pin "A11") (pinfunction "P0[4]/I2S_RX_SCK/CAN_RD2/T2_CAP0_A11") (pintype "bidirectional"))
    )
    (net (code "93") (name "/MMC_MISO1") (class "Default")
      (node (ref "IC24") (pin "C12") (pinfunction "P0[8]/I2S_TX_WS/SSP1_MISO/T2_MAT2/RTC_EV1_C12") (pintype "bidirectional"))
    )
    (net (code "94") (name "/MMC_MOSI1") (class "Default")
      (node (ref "IC24") (pin "A13") (pinfunction "P0[9]/I2S_TX_SDA/SSP1_MOSI/T2_MAT3/RTC_EV2_A13") (pintype "bidirectional"))
    )
    (net (code "95") (name "/MMC_SCK1") (class "Default")
      (node (ref "IC24") (pin "B12") (pinfunction "P0[7]/I2S_TX_SCK/SSP1_SCK/T2_MAT1/RTC_EV0_B12") (pintype "bidirectional"))
    )
    (net (code "96") (name "/MMC_SCL") (class "Default")
      (node (ref "IC24") (pin "N11") (pinfunction "P0[1]/CAN_TD1/U3_RXD/I2C1_SCL/U0_RXD_N11") (pintype "bidirectional"))
      (node (ref "IC78") (pin "19") (pinfunction "SCL_19") (pintype "input"))
    )
    (net (code "97") (name "/MMC_SDA") (class "Default")
      (node (ref "IC24") (pin "M10") (pinfunction "P0[0]/CAN_RD1/U3_TXD/I2C1_SDA/U0_TXD_M10") (pintype "bidirectional"))
      (node (ref "IC78") (pin "20") (pinfunction "SDA_20") (pintype "bidirectional"))
    )
    (net (code "98") (name "/MMC_SSEL1") (class "Default")
      (node (ref "IC24") (pin "D11") (pinfunction "P0[6]/I2S_RX_SDA/SSP1_SSEL/T2_MAT0/U1_RTS_D11") (pintype "bidirectional"))
    )
    (net (code "99") (name "/MOD_HANDLE") (class "Default")
      (node (ref "IC24") (pin "B14") (pinfunction "P4[13]/EMC_A[13]_B14") (pintype "bidirectional"))
      (node (ref "R193") (pin "1") (pinfunction "1_1") (pintype "passive"))
    )
    (net (code "100") (name "/P1") (class "Default")
      (node (ref "IC24") (pin "G5") (pinfunction "P3[3]/EMC_D[3]_G5") (pintype "bidirectional"))
      (node (ref "R204") (pin "2") (pinfunction "2_2") (pintype "passive"))
      (node (ref "R205") (pin "2") (pinfunction "2_2") (pintype "passive"))
      (node (ref "R206") (pin "2") (pinfunction "2_2") (pintype "passive"))
    )
    (net (code "101") (name "/P2") (class "Default")
      (node (ref "IC24") (pin "D3") (pinfunction "P3[4]/EMC_D[4]_D3") (pintype "bidirectional"))
      (node (ref "R210") (pin "2") (pinfunction "2_2") (pintype "passive"))
    )
    (net (code "102") (name "/P2_BLUE") (class "Default")
      (node (ref "LD1") (pin "1") (pinfunction "C_1") (pintype "passive"))
      (node (ref "R210") (pin "1") (pinfunction "1_1") (pintype "passive"))
    )
    (net (code "103") (name "/P3") (class "Default")
      (node (ref "IC24") (pin "E3") (pinfunction "P3[5]/EMC_D[5]_E3") (pintype "bidirectional"))
      (node (ref "R211") (pin "2") (pinfunction "2_2") (pintype "passive"))
    )
    (net (code "104") (name "/P3_GREEN") (class "Default")
      (node (ref "LD2") (pin "1") (pinfunction "C_1") (pintype "passive"))
      (node (ref "R211") (pin "1") (pinfunction "1_1") (pintype "passive"))
    )
    (net (code "105") (name "/P4") (class "Default")
      (node (ref "IC24") (pin "L7") (pinfunction "P1[25]/~{USB_LS1}/~{USB_HSTEN1}/T1_MAT1/MC_1A/CLKOUT_L7") (pintype "bidirectional"))
      (node (ref "R212") (pin "2") (pinfunction "2_2") (pintype "passive"))
    )
    (net (code "106") (name "/P4_RED") (class "Default")
      (node (ref "R212") (pin "1") (pinfunction "1_1") (pintype "passive"))
      (node (ref "U4") (pin "1") (pinfunction "C_1") (pintype "passive"))
    )
    (net (code "107") (name "/P12V0_OK") (class "Default")
      (node (ref "IC24") (pin "B2") (pinfunction "P3[11]/EMC_D[11]_B2") (pintype "bidirectional"))
    )
    (net (code "108") (name "/PGOOD_ADC_AVCC") (class "Default")
      (node (ref "IC24") (pin "F1") (pinfunction "P3[14]/EMC_D[14]_F1") (pintype "bidirectional"))
    )
    (net (code "109") (name "/PGOOD_AMS_CLK_P3V3") (class "Default")
      (node (ref "IC24") (pin "A1") (pinfunction "P3[12]/EMC_D[12]_A1") (pintype "bidirectional"))
    )
    (net (code "110") (name "/PGOOD_DAC_AVCC") (class "Default")
      (node (ref "IC24") (pin "H11") (pinfunction "P2[9]/USB_CONNECT1/U2_RXD/U4_RXD/ENET_MDIO_H11") (pintype "bidirectional"))
    )
    (net (code "111") (name "/PGOOD_DAC_AVCCAUX") (class "Default")
      (node (ref "IC24") (pin "G14") (pinfunction "P2[8]/CAN_TD2/U2_TXD/U1_CTS/ENET_MDC_G14") (pintype "bidirectional"))
    )
    (net (code "112") (name "/PGOOD_LTM0") (class "Default")
      (node (ref "IC24") (pin "A4") (pinfunction "P3[9]/EMC_D[9]_A4") (pintype "bidirectional"))
    )
    (net (code "113") (name "/PGOOD_LTM1") (class "Default")
      (node (ref "IC24") (pin "A6") (pinfunction "P3[8]/EMC_D[8]_A6") (pintype "bidirectional"))
    )
    (net (code "114") (name "/PGOOD_LTM2") (class "Default")
      (node (ref "IC24") (pin "G3") (pinfunction "P3[7]/EMC_D[7]_G3") (pintype "bidirectional"))
    )
    (net (code "115") (name "/PGOOD_MGT1V8") (class "Default")
      (node (ref "IC24") (pin "C1") (pinfunction "P3[13]/EMC_D[13]_C1") (pintype "bidirectional"))
    )
    (net (code "116") (name "/PGOOD_MGTRAVCC") (class "Default")
      (node (ref "IC24") (pin "G11") (pinfunction "P2[7]/CAN_RD2/U1_RTS_G11") (pintype "bidirectional"))
    )
    (net (code "117") (name "/PGOOD_P5V0") (class "Default")
      (node (ref "IC24") (pin "G4") (pinfunction "P3[15]/EMC_D[15]_G4") (pintype "bidirectional"))
    )
    (net (code "118") (name "/PGOOD_VCCINT_IO") (class "Default")
      (node (ref "IC24") (pin "B3") (pinfunction "P3[10]/EMC_D[10]_B3") (pintype "bidirectional"))
    )
    (net (code "119") (name "/PHY_RESETn") (class "Default")
      (node (ref "IC24") (pin "F5") (pinfunction "P0[23]/ADC0_IN[0]/I2S_RX_SCK/T3_CAP0_F5") (pintype "bidirectional"))
    )
    (net (code "120") (name "/PS_POR_B") (class "Default")
      (node (ref "IC24") (pin "C4") (pinfunction "P5[4]/U0_OE/T3_MAT3/U4_TXD_C4") (pintype "bidirectional"))
    )
    (net (code "121") (name "/PS_SRST") (class "Default")
      (node (ref "IC24") (pin "H12") (pinfunction "P4[9]/EMC_A[9]_H12") (pintype "bidirectional"))
      (node (ref "R196") (pin "2") (pinfunction "2_2") (pintype "passive"))
    )
    (net (code "122") (name "/RTM_JTAG_Override") (class "Default")
      (node (ref "IC24") (pin "D12") (pinfunction "P2[0]/PWM1[1]/U1_TXD_D12") (pintype "bidirectional"))
    )
    (net (code "123") (name "/RTM_PS#") (class "Default")
      (node (ref "D6") (pin "1") (pinfunction "C_1") (pintype "passive"))
      (node (ref "R202") (pin "1") (pinfunction "1_1") (pintype "passive"))
      (node (ref "R203") (pin "1") (pinfunction "1_1") (pintype "passive"))
    )
    (net (code "124") (name "/RUN") (class "Default")
      (node (ref "IC24") (pin "B9") (pinfunction "P4[29]/~{EMC_BLS3}/U3_RXD/T2_MAT1/I2C2_SCL_B9") (pintype "bidirectional"))
    )
    (net (code "125") (name "/SDCLK") (class "Default")
      (node (ref "B5") (pin "1") (pinfunction "1_1") (pintype "passive"))
      (node (ref "IC24") (pin "J10") (pinfunction "P0[19]/U1_DSR/SD_CLK/I2C1_SDA_J10") (pintype "bidirectional"))
    )
    (net (code "126") (name "/SDCMD") (class "Default")
      (node (ref "B6") (pin "1") (pinfunction "1_1") (pintype "passive"))
      (node (ref "IC24") (pin "K14") (pinfunction "P0[20]/U1_DTR/SD_CMD/I2C1_SCL_K14") (pintype "bidirectional"))
    )
    (net (code "127") (name "/SDDAT0") (class "Default")
      (node (ref "B8") (pin "1") (pinfunction "1_1") (pintype "passive"))
      (node (ref "IC24") (pin "L14") (pinfunction "P0[22]/U1_RTS/SD_DAT[0]/U4_TXD/CAN_TD1_L14") (pintype "bidirectional"))
    )
    (net (code "128") (name "/SDDAT1") (class "Default")
      (node (ref "B9") (pin "1") (pinfunction "1_1") (pintype "passive"))
      (node (ref "IC24") (pin "M12") (pinfunction "P2[11]/~{EINT1}/SD_DAT[1]/I2S_TX_SCK_M12") (pintype "bidirectional"))
    )
    (net (code "129") (name "/SDDAT2") (class "Default")
      (node (ref "B10") (pin "1") (pinfunction "1_1") (pintype "passive"))
      (node (ref "IC24") (pin "N14") (pinfunction "P2[12]/~{EINT2}/SD_DAT[2]/I2S_TX_WS_N14") (pintype "bidirectional"))
    )
    (net (code "130") (name "/SDDAT3") (class "Default")
      (node (ref "B11") (pin "1") (pinfunction "1_1") (pintype "passive"))
      (node (ref "IC24") (pin "M11") (pinfunction "P2[13]/~{EINT3}/SD_DAT[3]/I2S_TX_SDA_M11") (pintype "bidirectional"))
    )
    (net (code "131") (name "/SDPWR") (class "Default")
      (node (ref "B7") (pin "1") (pinfunction "1_1") (pintype "passive"))
      (node (ref "IC24") (pin "K11") (pinfunction "P0[21]/U1_RI/SD_PWR/U4_OE/CAN_RD1/U4_SCLK_K11") (pintype "bidirectional"))
    )
    (net (code "132") (name "/SDRAM_PGOOD") (class "Default")
      (node (ref "IC24") (pin "C14") (pinfunction "P2[1]/PWM1[2]/U1_RXD_C14") (pintype "bidirectional"))
      (node (ref "R37") (pin "1") (pinfunction "1_1") (pintype "passive"))
    )
    (net (code "133") (name "/SSP0_MISO") (class "Default")
      (node (ref "IC24") (pin "J12") (pinfunction "P0[17]/U1_CTS/SSP0_MISO_J12") (pintype "bidirectional"))
      (node (ref "IC6") (pin "8") (pinfunction "DQ1_8") (pintype "bidirectional"))
    )
    (net (code "134") (name "/SSP0_MOSI") (class "Default")
      (node (ref "IC24") (pin "J13") (pinfunction "P0[18]/U1_DCD/SSP0_MOSI_J13") (pintype "bidirectional"))
      (node (ref "IC6") (pin "15") (pinfunction "DQ0_15") (pintype "bidirectional"))
    )
    (net (code "135") (name "/SSP0_SCK") (class "Default")
      (node (ref "IC24") (pin "H13") (pinfunction "P0[15]/U1_TXD/SSP0_SCK_H13") (pintype "bidirectional"))
      (node (ref "IC6") (pin "16") (pinfunction "C_16") (pintype "input"))
    )
    (net (code "136") (name "/SSP0_SSEL") (class "Default")
      (node (ref "IC24") (pin "H14") (pinfunction "P0[16]/U1_RXD/SSP0_SSEL_H14") (pintype "bidirectional"))
      (node (ref "IC6") (pin "7") (pinfunction "~{S}_7") (pintype "input"))
    )
    (net (code "137") (name "/SW") (class "Default")
      (node (ref "IC24") (pin "F10") (pinfunction "P4[12]/EMC_A[12]_F10") (pintype "bidirectional"))
      (node (ref "R192") (pin "1") (pinfunction "1_1") (pintype "passive"))
    )
    (net (code "138") (name "/TRACECLK") (class "Default")
      (node (ref "IC24") (pin "F13") (pinfunction "P2[6]/PWM1_CAP0/U1_RI/T2_CAP0/U2_OE/TRACECLK_F13") (pintype "bidirectional"))
    )
    (net (code "139") (name "/TRACEDATA0") (class "Default")
      (node (ref "IC24") (pin "F12") (pinfunction "P2[5]/PWM1[6]/U1_DTR/T2_MAT0/TRACEDATA[0]_F12") (pintype "bidirectional"))
    )
    (net (code "140") (name "/TRACEDATA1") (class "Default")
      (node (ref "IC24") (pin "E14") (pinfunction "P2[4]/PWM1[5]/U1_DSR/T2_MAT1/TRACEDATA[1]_E14") (pintype "bidirectional"))
    )
    (net (code "141") (name "/TRACEDATA2") (class "Default")
      (node (ref "IC24") (pin "E13") (pinfunction "P2[3]/PWM1[4]/U1_DCD/T2_MAT2/TRACEDATA[2]_E13") (pintype "bidirectional"))
    )
    (net (code "142") (name "/TRACEDATA3") (class "Default")
      (node (ref "IC24") (pin "E11") (pinfunction "P2[2]/PWM1[3]/U1_CTS/T2_MAT3/TRACEDATA[3]_E11") (pintype "bidirectional"))
    )
    (net (code "153") (name "GND") (class "Default")
      (node (ref "C292") (pin "1") (pinfunction "1_1") (pintype "passive"))
      (node (ref "C92") (pin "1") (pinfunction "1_1") (pintype "passive"))
      (node (ref "D4") (pin "2") (pinfunction "A_2") (pintype "passive"))
      (node (ref "D5") (pin "2") (pinfunction "A_2") (pintype "passive"))
      (node (ref "D6") (pin "2") (pinfunction "A_2") (pintype "passive"))
      (node (ref "D7") (pin "2") (pinfunction "A_2") (pintype "passive"))
      (node (ref "D8") (pin "2") (pinfunction "A_2") (pintype "passive"))
      (node (ref "D9") (pin "2") (pinfunction "A_2") (pintype "passive"))
      (node (ref "IC6") (pin "10") (pinfunction "VSS_10") (pintype "power_in"))
      (node (ref "IC78") (pin "23") (pinfunction "A1_23") (pintype "bidirectional"))
      (node (ref "IC78") (pin "25") (pinfunction "EP_25") (pintype "power_in"))
      (node (ref "IC78") (pin "9") (pinfunction "GND_9") (pintype "power_in"))
      (node (ref "R196") (pin "1") (pinfunction "1_1") (pintype "passive"))
      (node (ref "R217") (pin "1") (pinfunction "1_1") (pintype "passive"))
      (node (ref "R218") (pin "1") (pinfunction "1_1") (pintype "passive"))
      (node (ref "R219") (pin "1") (pinfunction "1_1") (pintype "passive"))
      (node (ref "R220") (pin "1") (pinfunction "1_1") (pintype "passive"))
      (node (ref "R379") (pin "2") (pinfunction "2_2") (pintype "passive"))
    )
    (net (code "154") (name "Net-(IC6-~{HOLD}{slash}DQ3)") (class "Default")
      (node (ref "IC6") (pin "1") (pinfunction "~{HOLD}/DQ3_1") (pintype "bidirectional"))
      (node (ref "R48") (pin "1") (pinfunction "1_1") (pintype "passive"))
    )
    (net (code "155") (name "Net-(IC6-~{RESET})") (class "Default")
      (node (ref "IC6") (pin "3") (pinfunction "~{RESET}_3") (pintype "input"))
      (node (ref "R49") (pin "1") (pinfunction "1_1") (pintype "passive"))
    )
    (net (code "156") (name "Net-(IC6-~{W}{slash}DQ2)") (class "Default")
      (node (ref "IC6") (pin "9") (pinfunction "~{W}/DQ2_9") (pintype "bidirectional"))
      (node (ref "R47") (pin "1") (pinfunction "1_1") (pintype "passive"))
    )
    (net (code "157") (name "Net-(IC24A-P0[10]{slash}U2_TXD{slash}I2C2_SDA{slash}T3_MAT0)") (class "Default")
      (node (ref "IC24") (pin "L10") (pinfunction "P0[10]/U2_TXD/I2C2_SDA/T3_MAT0_L10") (pintype "bidirectional"))
      (node (ref "R198") (pin "2") (pinfunction "2_2") (pintype "passive"))
    )
    (net (code "158") (name "Net-(IC24A-P0[11]{slash}U2_RXD{slash}I2C2_SCL{slash}T3_MAT1)") (class "Default")
      (node (ref "IC24") (pin "P12") (pinfunction "P0[11]/U2_RXD/I2C2_SCL/T3_MAT1_P12") (pintype "bidirectional"))
      (node (ref "R199") (pin "2") (pinfunction "2_2") (pintype "passive"))
    )
    (net (code "159") (name "Net-(IC24A-P0[29]{slash}USB_D+1{slash}~{EINT0})") (class "Default")
      (node (ref "IC24") (pin "K5") (pinfunction "P0[29]/USB_D+1/~{EINT0}_K5") (pintype "bidirectional"))
      (node (ref "R203") (pin "2") (pinfunction "2_2") (pintype "passive"))
    )
    (net (code "160") (name "Net-(IC78-A0)") (class "Default")
      (node (ref "IC78") (pin "18") (pinfunction "A0_18") (pintype "bidirectional"))
      (node (ref "R379") (pin "1") (pinfunction "1_1") (pintype "passive"))
    )
    (net (code "161") (name "Net-(IC78-~{INT})") (class "Default")
      (node (ref "IC78") (pin "22") (pinfunction "~{INT}_22") (pintype "output"))
      (node (ref "R423") (pin "1") (pinfunction "1_1") (pintype "passive"))
    )
    (net (code "162") (name "Net-(IC78-~{RESET})") (class "Default")
      (node (ref "IC78") (pin "24") (pinfunction "~{RESET}_24") (pintype "input"))
      (node (ref "R257") (pin "1") (pinfunction "1_1") (pintype "passive"))
    )
    (net (code "163") (name "P3V3") (class "Default")
      (node (ref "R37") (pin "2") (pinfunction "2_2") (pintype "passive"))
    )
    (net (code "164") (name "P3V3MP") (class "Default")
      (node (ref "C292") (pin "2") (pinfunction "2_2") (pintype "passive"))
      (node (ref "C92") (pin "2") (pinfunction "2_2") (pintype "passive"))
      (node (ref "IC6") (pin "2") (pinfunction "VCC_2") (pintype "power_in"))
      (node (ref "IC78") (pin "21") (pinfunction "VCC_21") (pintype "power_in"))
      (node (ref "LD1") (pin "2") (pinfunction "A_2") (pintype "passive"))
      (node (ref "LD2") (pin "2") (pinfunction "A_2") (pintype "passive"))
      (node (ref "R191") (pin "2") (pinfunction "2_2") (pintype "passive"))
      (node (ref "R192") (pin "2") (pinfunction "2_2") (pintype "passive"))
      (node (ref "R193") (pin "2") (pinfunction "2_2") (pintype "passive"))
      (node (ref "R197") (pin "1") (pinfunction "1_1") (pintype "passive"))
      (node (ref "R200") (pin "1") (pinfunction "1_1") (pintype "passive"))
      (node (ref "R201") (pin "1") (pinfunction "1_1") (pintype "passive"))
      (node (ref "R202") (pin "2") (pinfunction "2_2") (pintype "passive"))
      (node (ref "R213") (pin "1") (pinfunction "1_1") (pintype "passive"))
      (node (ref "R214") (pin "1") (pinfunction "1_1") (pintype "passive"))
      (node (ref "R215") (pin "1") (pinfunction "1_1") (pintype "passive"))
      (node (ref "R216") (pin "1") (pinfunction "1_1") (pintype "passive"))
      (node (ref "R257") (pin "2") (pinfunction "2_2") (pintype "passive"))
      (node (ref "R423") (pin "2") (pinfunction "2_2") (pintype "passive"))
      (node (ref "R47") (pin "2") (pinfunction "2_2") (pintype "passive"))
      (node (ref "R48") (pin "2") (pinfunction "2_2") (pintype "passive"))
      (node (ref "R49") (pin "2") (pinfunction "2_2") (pintype "passive"))
      (node (ref "U4") (pin "2") (pinfunction "A_2") (pintype "passive"))
    )
    (net (code "165") (name "unconnected-(IC6-DNU-Pad4)") (class "Default")
      (node (ref "IC6") (pin "4") (pinfunction "DNU_4") (pintype "passive"))
    )
    (net (code "166") (name "unconnected-(IC6-DNU-Pad5)") (class "Default")
      (node (ref "IC6") (pin "5") (pinfunction "DNU_5") (pintype "passive"))
    )
    (net (code "167") (name "unconnected-(IC6-DNU-Pad6)") (class "Default")
      (node (ref "IC6") (pin "6") (pinfunction "DNU_6") (pintype "passive"))
    )
    (net (code "168") (name "unconnected-(IC6-DNU-Pad11)") (class "Default")
      (node (ref "IC6") (pin "11") (pinfunction "DNU_11") (pintype "passive"))
    )
    (net (code "169") (name "unconnected-(IC6-DNU-Pad12)") (class "Default")
      (node (ref "IC6") (pin "12") (pinfunction "DNU_12") (pintype "passive"))
    )
    (net (code "170") (name "unconnected-(IC6-DNU-Pad13)") (class "Default")
      (node (ref "IC6") (pin "13") (pinfunction "DNU_13") (pintype "passive"))
    )
    (net (code "171") (name "unconnected-(IC6-DNU-Pad14)") (class "Default")
      (node (ref "IC6") (pin "14") (pinfunction "DNU_14") (pintype "passive"))
    )
    (net (code "172") (name "unconnected-(IC24A-P0[24]{slash}ADC0_IN[1]{slash}I2S_RX_WS{slash}T3_CAP1-PadE1)") (class "Default")
      (node (ref "IC24") (pin "E1") (pinfunction "P0[24]/ADC0_IN[1]/I2S_RX_WS/T3_CAP1_E1") (pintype "bidirectional"))
    )
    (net (code "173") (name "unconnected-(IC24A-P0[25]{slash}ADC0_IN[2]{slash}I2S_RX_SDA{slash}U3_TXD-PadE4)") (class "Default")
      (node (ref "IC24") (pin "E4") (pinfunction "P0[25]/ADC0_IN[2]/I2S_RX_SDA/U3_TXD_E4") (pintype "bidirectional"))
    )
    (net (code "174") (name "unconnected-(IC24A-P0[26]{slash}ADC0_IN[3]{slash}DAC_OUT{slash}U3_RXD-PadD1)") (class "Default")
      (node (ref "IC24") (pin "D1") (pinfunction "P0[26]/ADC0_IN[3]/DAC_OUT/U3_RXD_D1") (pintype "bidirectional"))
    )
    (net (code "175") (name "unconnected-(IC24A-P0[30]{slash}USB_D-1{slash}~{EINT1}-PadN4)") (class "Default")
      (node (ref "IC24") (pin "N4") (pinfunction "P0[30]/USB_D-1/~{EINT1}_N4") (pintype "bidirectional"))
    )
    (net (code "176") (name "unconnected-(IC24A-P1[5]{slash}ENET_TX_ER{slash}SD_PWR{slash}PWM0[3]-PadB13)") (class "Default")
      (node (ref "IC24") (pin "B13") (pinfunction "P1[5]/ENET_TX_ER/SD_PWR/PWM0[3]_B13") (pintype "bidirectional"))
    )
    (net (code "177") (name "unconnected-(IC24A-P1[19]{slash}~{USB_TX_E1}{slash}~{USB_PPWR1}{slash}T1_CAP1{slash}MC_0A{slash}SSP1_SCK{slash}U2_OE-PadP5)") (class "Default")
      (node (ref "IC24") (pin "P5") (pinfunction "P1[19]/~{USB_TX_E1}/~{USB_PPWR1}/T1_CAP1/MC_0A/SSP1_SCK/U2_OE_P5") (pintype "bidirectional"))
    )
    (net (code "178") (name "unconnected-(IC24A-P1[22]{slash}USB_RCV1{slash}USB_PWRD1{slash}T1_MAT0{slash}MC_0B{slash}SSP1_MOSI-PadM6)") (class "Default")
      (node (ref "IC24") (pin "M6") (pinfunction "P1[22]/USB_RCV1/USB_PWRD1/T1_MAT0/MC_0B/SSP1_MOSI_M6") (pintype "bidirectional"))
    )
    (net (code "179") (name "unconnected-(IC24A-P1[26]{slash}~{USB_SSPND1}{slash}PWM1[6]{slash}T0_CAP0{slash}MC_1B{slash}SSP1_SSEL-PadP8)") (class "Default")
      (node (ref "IC24") (pin "P8") (pinfunction "P1[26]/~{USB_SSPND1}/PWM1[6]/T0_CAP0/MC_1B/SSP1_SSEL_P8") (pintype "bidirectional"))
    )
    (net (code "180") (name "unconnected-(IC24A-P1[27]{slash}~{USB_INT1}{slash}~{USB_OVRCR1}{slash}T0_CAP1{slash}CLKOUT-PadM9)") (class "Default")
      (node (ref "IC24") (pin "M9") (pinfunction "P1[27]/~{USB_INT1}/~{USB_OVRCR1}/T0_CAP1/CLKOUT_M9") (pintype "bidirectional"))
    )
    (net (code "181") (name "unconnected-(IC24A-P1[28]{slash}USB_SCL1{slash}PWM1_CAP0{slash}T0_MAT0{slash}MC_2A{slash}SSP0_SSEL-PadP10)") (class "Default")
      (node (ref "IC24") (pin "P10") (pinfunction "P1[28]/USB_SCL1/PWM1_CAP0/T0_MAT0/MC_2A/SSP0_SSEL_P10") (pintype "bidirectional"))
    )
    (net (code "182") (name "unconnected-(IC24A-P1[29]{slash}USB_SDA1{slash}PWM1_CAP1{slash}T0_MAT1{slash}MC_2B{slash}U4_TXD-PadN10)") (class "Default")
      (node (ref "IC24") (pin "N10") (pinfunction "P1[29]/USB_SDA1/PWM1_CAP1/T0_MAT1/MC_2B/U4_TXD_N10") (pintype "bidirectional"))
    )
    (net (code "183") (name "unconnected-(IC24A-P1[30]{slash}USB_PWRD2{slash}USB_VBUS{slash}ADC0_IN[4]{slash}I2C0_SDA{slash}U3_OE-PadK3)") (class "Default")
      (node (ref "IC24") (pin "K3") (pinfunction "P1[30]/USB_PWRD2/USB_VBUS/ADC0_IN[4]/I2C0_SDA/U3_OE_K3") (pintype "bidirectional"))
    )
    (net (code "184") (name "unconnected-(IC24A-P1[31]{slash}~{USB_OVRCR2}{slash}SSP1_SCK{slash}ADC0_IN[5]{slash}I2C0_SCL-PadK2)") (class "Default")
      (node (ref "IC24") (pin "K2") (pinfunction "P1[31]/~{USB_OVRCR2}/SSP1_SCK/ADC0_IN[5]/I2C0_SCL_K2") (pintype "bidirectional"))
    )
    (net (code "185") (name "unconnected-(IC24B-P2[20]{slash}~{EMC_DYCS0}-PadP6)") (class "Default")
      (node (ref "IC24") (pin "P6") (pinfunction "P2[20]/~{EMC_DYCS0}_P6") (pintype "bidirectional"))
    )
    (net (code "186") (name "unconnected-(IC24B-P2[21]{slash}~{EMC_DYCS1}-PadN8)") (class "Default")
      (node (ref "IC24") (pin "N8") (pinfunction "P2[21]/~{EMC_DYCS1}_N8") (pintype "bidirectional"))
    )
    (net (code "187") (name "unconnected-(IC24B-P3[6]{slash}EMC_D[6]-PadF4)") (class "Default")
      (node (ref "IC24") (pin "F4") (pinfunction "P3[6]/EMC_D[6]_F4") (pintype "bidirectional"))
    )
    (net (code "188") (name "unconnected-(IC24C-P4[0]{slash}EMC_A[0]-PadL6)") (class "Default")
      (node (ref "IC24") (pin "L6") (pinfunction "P4[0]/EMC_A[0]_L6") (pintype "bidirectional"))
    )
    (net (code "189") (name "unconnected-(IC24C-P4[1]{slash}EMC_A[1]-PadM7)") (class "Default")
      (node (ref "IC24") (pin "M7") (pinfunction "P4[1]/EMC_A[1]_M7") (pintype "bidirectional"))
    )
    (net (code "190") (name "unconnected-(IC24C-P4[2]{slash}EMC_A[2]-PadM8)") (class "Default")
      (node (ref "IC24") (pin "M8") (pinfunction "P4[2]/EMC_A[2]_M8") (pintype "bidirectional"))
    )
    (net (code "191") (name "unconnected-(IC24C-P4[3]{slash}EMC_A[3]-PadK9)") (class "Default")
      (node (ref "IC24") (pin "K9") (pinfunction "P4[3]/EMC_A[3]_K9") (pintype "bidirectional"))
    )
    (net (code "192") (name "unconnected-(IC24C-P4[4]{slash}EMC_A[4]-PadP13)") (class "Default")
      (node (ref "IC24") (pin "P13") (pinfunction "P4[4]/EMC_A[4]_P13") (pintype "bidirectional"))
    )
    (net (code "193") (name "unconnected-(IC24C-P4[5]{slash}EMC_A[5]-PadH10)") (class "Default")
      (node (ref "IC24") (pin "H10") (pinfunction "P4[5]/EMC_A[5]_H10") (pintype "bidirectional"))
    )
    (net (code "194") (name "unconnected-(IC24C-P4[6]{slash}EMC_A[6]-PadK10)") (class "Default")
      (node (ref "IC24") (pin "K10") (pinfunction "P4[6]/EMC_A[6]_K10") (pintype "bidirectional"))
    )
    (net (code "195") (name "unconnected-(IC24C-P4[7]{slash}EMC_A[7]-PadK12)") (class "Default")
      (node (ref "IC24") (pin "K12") (pinfunction "P4[7]/EMC_A[7]_K12") (pintype "bidirectional"))
    )
    (net (code "196") (name "unconnected-(IC24C-P4[10]{slash}EMC_A[10]-PadG12)") (class "Default")
      (node (ref "IC24") (pin "G12") (pinfunction "P4[10]/EMC_A[10]_G12") (pintype "bidirectional"))
    )
    (net (code "197") (name "unconnected-(IC24C-P4[14]{slash}EMC_A[14]-PadE8)") (class "Default")
      (node (ref "IC24") (pin "E8") (pinfunction "P4[14]/EMC_A[14]_E8") (pintype "bidirectional"))
    )
    (net (code "198") (name "unconnected-(IC24C-P4[15]{slash}EMC_A[15]-PadC10)") (class "Default")
      (node (ref "IC24") (pin "C10") (pinfunction "P4[15]/EMC_A[15]_C10") (pintype "bidirectional"))
    )
    (net (code "199") (name "unconnected-(IC24C-P4[16]{slash}EMC_A[16]-PadN12)") (class "Default")
      (node (ref "IC24") (pin "N12") (pinfunction "P4[16]/EMC_A[16]_N12") (pintype "bidirectional"))
    )
    (net (code "200") (name "unconnected-(IC24C-P4[24]{slash}~{EMC_OE}-PadC8)") (class "Default")
      (node (ref "IC24") (pin "C8") (pinfunction "P4[24]/~{EMC_OE}_C8") (pintype "bidirectional"))
    )
    (net (code "201") (name "unconnected-(IC24C-P4[25]{slash}~{EMC_WE}-PadD9)") (class "Default")
      (node (ref "IC24") (pin "D9") (pinfunction "P4[25]/~{EMC_WE}_D9") (pintype "bidirectional"))
    )
    (net (code "202") (name "unconnected-(IC24C-P4[26]{slash}~{EMC_BLS0}-PadK13)") (class "Default")
      (node (ref "IC24") (pin "K13") (pinfunction "P4[26]/~{EMC_BLS0}_K13") (pintype "bidirectional"))
    )
    (net (code "203") (name "unconnected-(IC24C-P4[28]{slash}~{EMC_BLS2}{slash}U3_TXD{slash}T2_MAT0-PadD10)") (class "Default")
      (node (ref "IC24") (pin "D10") (pinfunction "P4[28]/~{EMC_BLS2}/U3_TXD/T2_MAT0_D10") (pintype "bidirectional"))
    )
    (net (code "204") (name "unconnected-(IC24C-P4[31]{slash}~{EMC_CS1}-PadE7)") (class "Default")
      (node (ref "IC24") (pin "E7") (pinfunction "P4[31]/~{EMC_CS1}_E7") (pintype "bidirectional"))
    )
    (net (code "205") (name "unconnected-(IC24C-P5[1]{slash}EMC_A[25]{slash}SSP2_MISO{slash}T2_MAT3-PadH1)") (class "Default")
      (node (ref "IC24") (pin "H1") (pinfunction "P5[1]/EMC_A[25]/SSP2_MISO/T2_MAT3_H1") (pintype "bidirectional"))
    )
    (net (code "206") (name "unconnected-(IC24C-P5[2]{slash}T3_MAT2{slash}I2C0_SDA-PadL12)") (class "Default")
      (node (ref "IC24") (pin "L12") (pinfunction "P5[2]/T3_MAT2/I2C0_SDA_L12") (pintype "bidirectional"))
    )
    (net (code "207") (name "unconnected-(IC24C-P5[3]{slash}U4_RXD{slash}I2C0_SCL-PadG10)") (class "Default")
      (node (ref "IC24") (pin "G10") (pinfunction "P5[3]/U4_RXD/I2C0_SCL_G10") (pintype "bidirectional"))
    )
  )
)
